# PiAndServos.net
KiCad netlist of a schematic drawn in Altium Designer
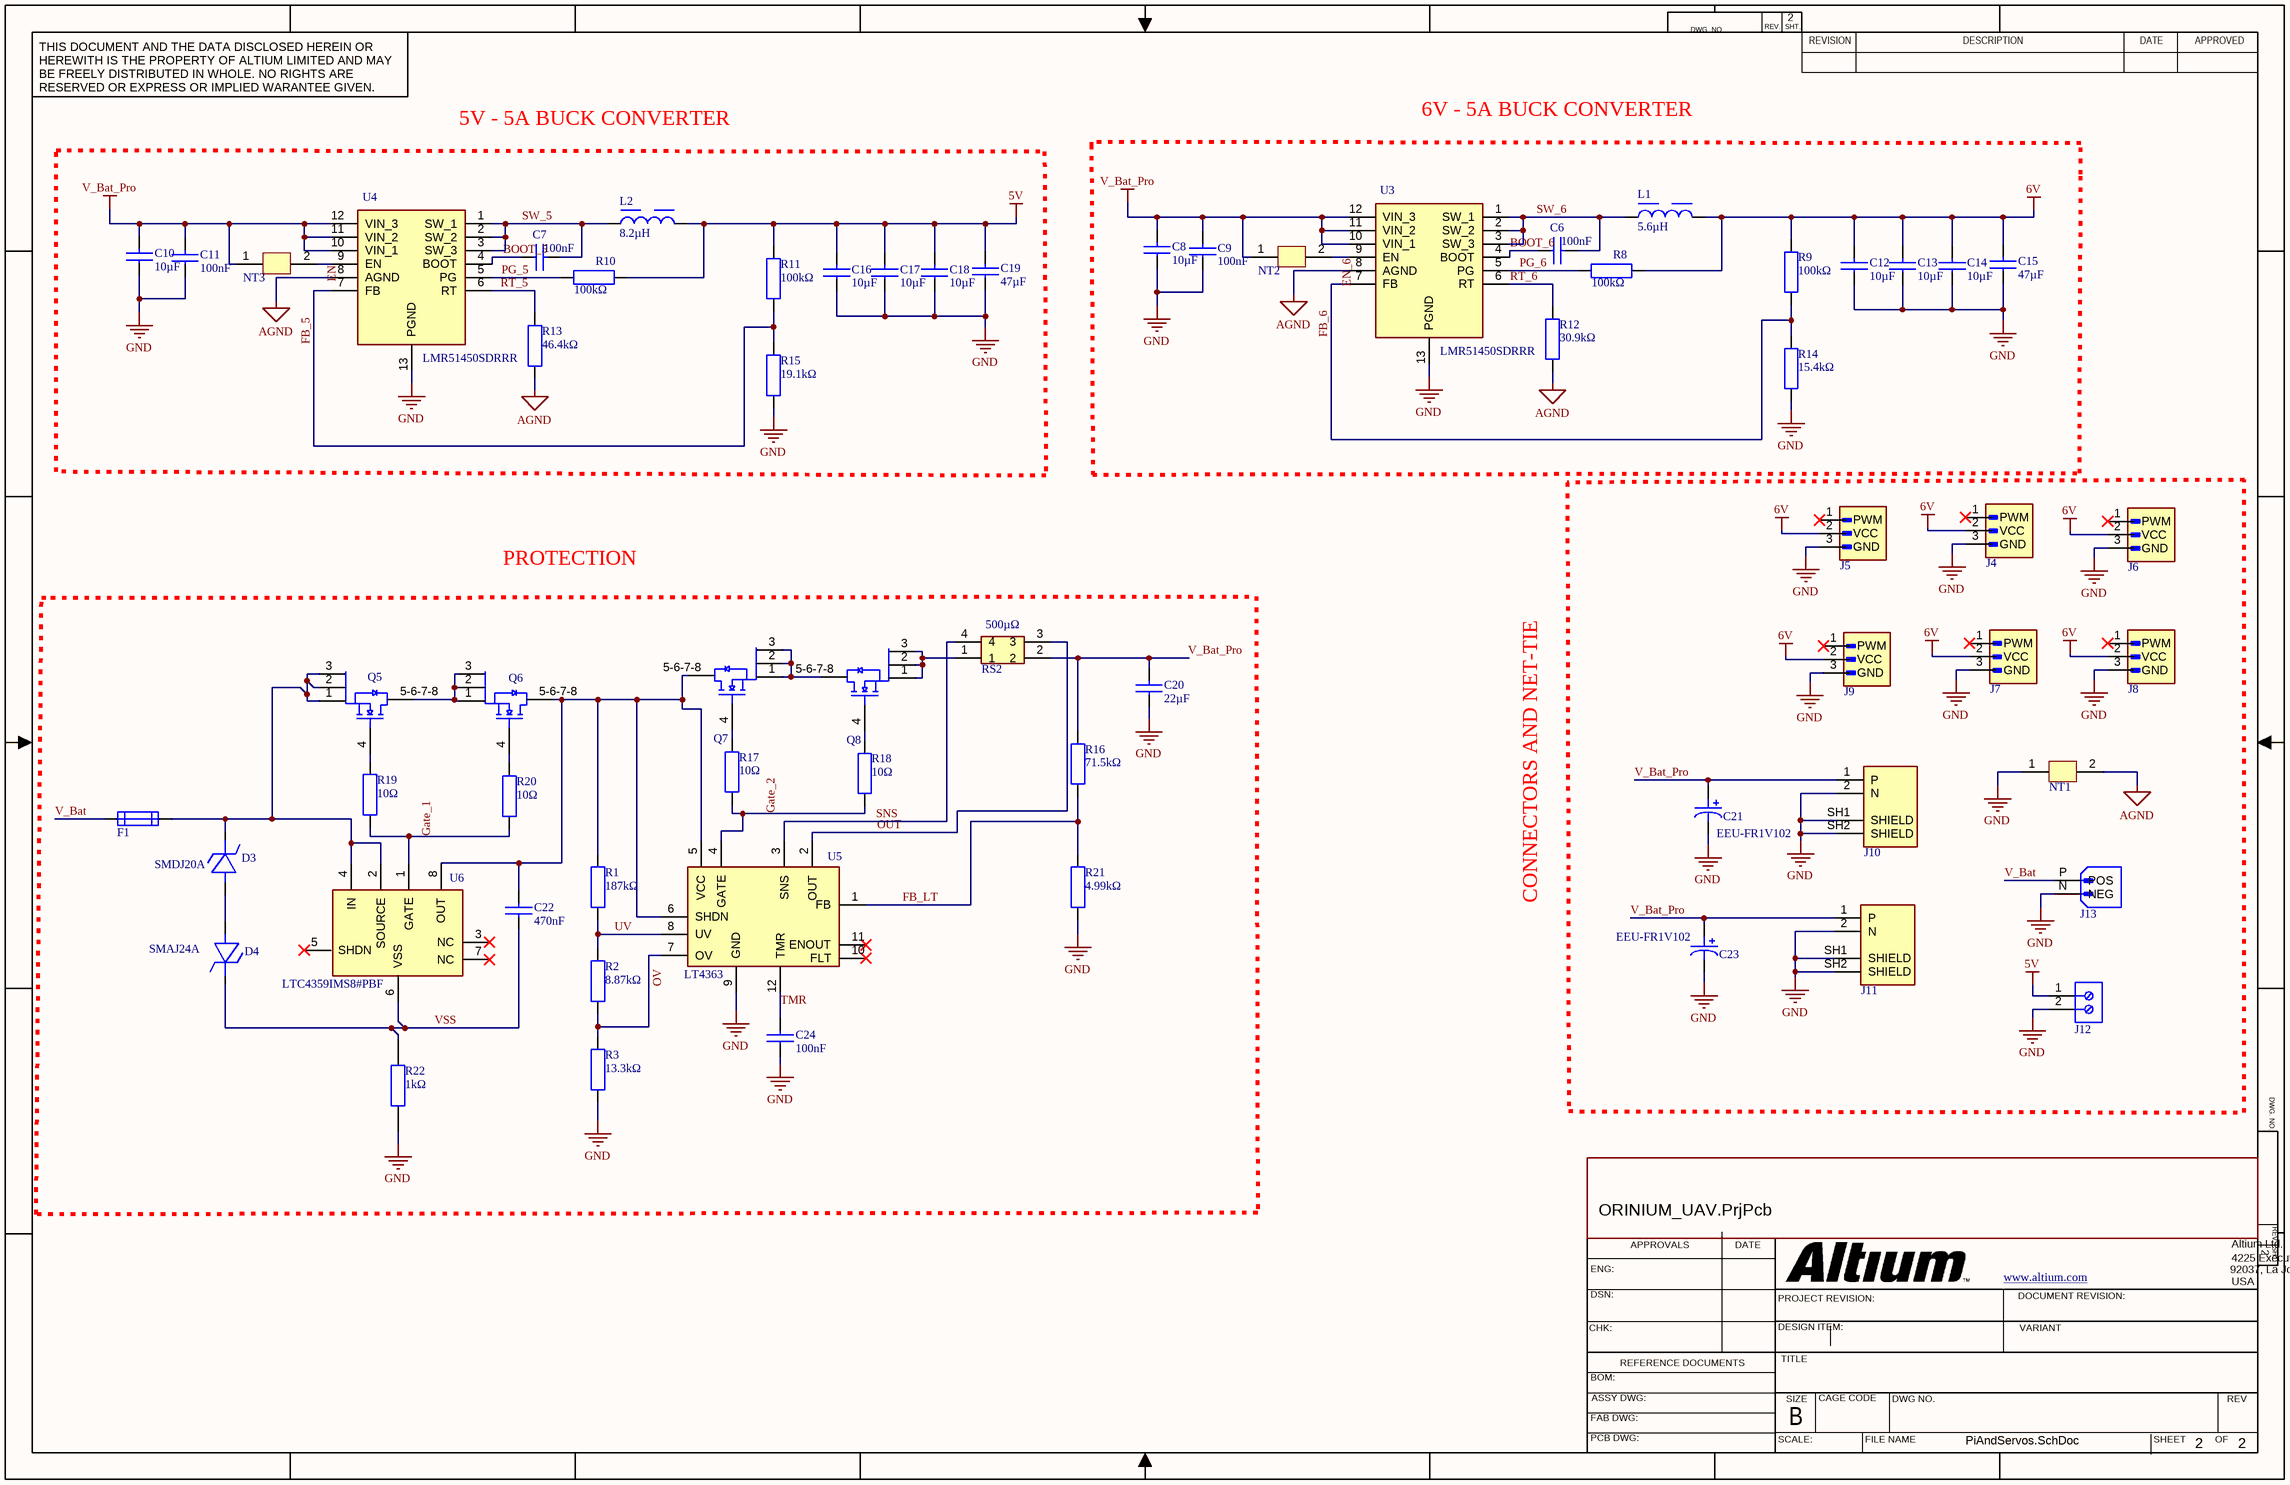
[diagram p0: PiAndServos.SchDoc]

(export (version "E")
  (design (tool "Eeschema 10.0.6"))
  (components
    (comp (ref "C6")
      (value "100nF")
      (footprint "CAP 0402")
      (description "16V 100nF X7R ±10% 0402 Multilayer Ceramic Capacitors MLCC - SMD/SMT ROHS")
      (fields
        (field (name "MANUFACTURER") "Murata")
        (field (name "MANUFACTURER PART NUMBER") "GRM155R71C104KA88D")
      )
      (libsource (lib "UAV") (part "GRM155R71C104KA88D"))
    )
    (comp (ref "C7")
      (value "100nF")
      (footprint "CAP 0402")
      (description "16V 100nF X7R ±10% 0402 Multilayer Ceramic Capacitors MLCC - SMD/SMT ROHS")
      (fields
        (field (name "MANUFACTURER") "Murata")
        (field (name "MANUFACTURER PART NUMBER") "GRM155R71C104KA88D")
      )
      (libsource (lib "UAV") (part "GRM155R71C104KA88D"))
    )
    (comp (ref "C8")
      (value "10µF")
      (footprint "CAP 1210")
      (description "50V 10uF X7R 卤20% 1210 Multilayer Ceramic Capacitors MLCC - SMD/SMT ROHS")
      (fields
        (field (name "MANUFACTURER") "TDK")
        (field (name "MANUFACTURER PART NUMBER") "C3225X7R1H106M250AC")
      )
      (libsource (lib "UAV") (part "C3225X7R1H106M250AC"))
    )
    (comp (ref "C9")
      (value "100nF")
      (footprint "CAP 0603")
      (description "Multilayer Ceramic Capacitor, CC Series, 0.1 - F, - 10%, X7R, 50 V, 0603 [1608 Metric]")
      (fields
        (field (name "MANUFACTURER") "Yageo Group")
        (field (name "MANUFACTURER PART NUMBER") "CC0603KRX7R9BB104")
      )
      (libsource (lib "UAV") (part "CC0603KRX7R9BB104"))
    )
    (comp (ref "C10")
      (value "10µF")
      (footprint "CAP 1210")
      (description "50V 10uF X7R 卤20% 1210 Multilayer Ceramic Capacitors MLCC - SMD/SMT ROHS")
      (fields
        (field (name "MANUFACTURER") "TDK")
        (field (name "MANUFACTURER PART NUMBER") "C3225X7R1H106M250AC")
      )
      (libsource (lib "UAV") (part "C3225X7R1H106M250AC"))
    )
    (comp (ref "C11")
      (value "100nF")
      (footprint "CAP 0603")
      (description "Multilayer Ceramic Capacitor, CC Series, 0.1 - F, - 10%, X7R, 50 V, 0603 [1608 Metric]")
      (fields
        (field (name "MANUFACTURER") "Yageo Group")
        (field (name "MANUFACTURER PART NUMBER") "CC0603KRX7R9BB104")
      )
      (libsource (lib "UAV") (part "CC0603KRX7R9BB104"))
    )
    (comp (ref "C12")
      (value "10µF")
      (footprint "CAP 1210")
      (description "50V 10uF X7R 卤20% 1210 Multilayer Ceramic Capacitors MLCC - SMD/SMT ROHS")
      (fields
        (field (name "MANUFACTURER") "TDK")
        (field (name "MANUFACTURER PART NUMBER") "C3225X7R1H106M250AC")
      )
      (libsource (lib "UAV") (part "C3225X7R1H106M250AC"))
    )
    (comp (ref "C13")
      (value "10µF")
      (footprint "CAP 1210")
      (description "50V 10uF X7R 卤20% 1210 Multilayer Ceramic Capacitors MLCC - SMD/SMT ROHS")
      (fields
        (field (name "MANUFACTURER") "TDK")
        (field (name "MANUFACTURER PART NUMBER") "C3225X7R1H106M250AC")
      )
      (libsource (lib "UAV") (part "C3225X7R1H106M250AC"))
    )
    (comp (ref "C14")
      (value "10µF")
      (footprint "CAP 1210")
      (description "50V 10uF X7R 卤20% 1210 Multilayer Ceramic Capacitors MLCC - SMD/SMT ROHS")
      (fields
        (field (name "MANUFACTURER") "TDK")
        (field (name "MANUFACTURER PART NUMBER") "C3225X7R1H106M250AC")
      )
      (libsource (lib "UAV") (part "C3225X7R1H106M250AC"))
    )
    (comp (ref "C15")
      (value "47µF")
      (footprint "CAP 1210")
      (description "16V 47uF X5R ±10% 1210 Multilayer Ceramic Capacitors MLCC - SMD/SMT ROHS")
      (fields
        (field (name "MANUFACTURER") "Murata")
        (field (name "MANUFACTURER PART NUMBER") "GRM32ER61C476KE15L")
      )
      (libsource (lib "UAV") (part "GRM32ER61C476KE15L"))
    )
    (comp (ref "C16")
      (value "10µF")
      (footprint "CAP 1210")
      (description "50V 10uF X7R 卤20% 1210 Multilayer Ceramic Capacitors MLCC - SMD/SMT ROHS")
      (fields
        (field (name "MANUFACTURER") "TDK")
        (field (name "MANUFACTURER PART NUMBER") "C3225X7R1H106M250AC")
      )
      (libsource (lib "UAV") (part "C3225X7R1H106M250AC"))
    )
    (comp (ref "C17")
      (value "10µF")
      (footprint "CAP 1210")
      (description "50V 10uF X7R 卤20% 1210 Multilayer Ceramic Capacitors MLCC - SMD/SMT ROHS")
      (fields
        (field (name "MANUFACTURER") "TDK")
        (field (name "MANUFACTURER PART NUMBER") "C3225X7R1H106M250AC")
      )
      (libsource (lib "UAV") (part "C3225X7R1H106M250AC"))
    )
    (comp (ref "C18")
      (value "10µF")
      (footprint "CAP 1210")
      (description "50V 10uF X7R 卤20% 1210 Multilayer Ceramic Capacitors MLCC - SMD/SMT ROHS")
      (fields
        (field (name "MANUFACTURER") "TDK")
        (field (name "MANUFACTURER PART NUMBER") "C3225X7R1H106M250AC")
      )
      (libsource (lib "UAV") (part "C3225X7R1H106M250AC"))
    )
    (comp (ref "C19")
      (value "47µF")
      (footprint "CAP 1210")
      (description "16V 47uF X5R ±10% 1210 Multilayer Ceramic Capacitors MLCC - SMD/SMT ROHS")
      (fields
        (field (name "MANUFACTURER") "Murata")
        (field (name "MANUFACTURER PART NUMBER") "GRM32ER61C476KE15L")
      )
      (libsource (lib "UAV") (part "GRM32ER61C476KE15L"))
    )
    (comp (ref "C20")
      (value "22µF")
      (footprint "CAP 2220")
      (description "50V 22uF X7R 卤20% 2220 Multilayer Ceramic Capacitors MLCC - SMD/SMT ROHS")
      (fields
        (field (name "MANUFACTURER") "TDK")
        (field (name "MANUFACTURER PART NUMBER") "C5750X7R1H226M250KB")
      )
      (libsource (lib "UAV") (part "C5750X7R1H226M250KB"))
    )
    (comp (ref "C21")
      (value "EEU-FR1V102")
      (footprint "CAP ALUM THT")
      (description "Radial Can ALUMINUM ELECTROLYTIC CAPACITOR FR 35V 1000muF ±20% 0.492Dia 12.50mm")
      (fields
        (field (name "MANUFACTURER") "Panasonic")
        (field (name "MANUFACTURER PART NUMBER") "EEUFR1V102")
      )
      (libsource (lib "UAV") (part "EEU-FR1V102"))
    )
    (comp (ref "C22")
      (value "470nF")
      (footprint "CAP 0603")
      (description "0612/0805/1206 Feedthru Ceramic Capacitors 1206 50V 47000pF")
      (fields
        (field (name "MANUFACTURER") "TAIYO YUDEN")
        (field (name "MANUFACTURER PART NUMBER") "MCASU168SB7474KTCA01")
      )
      (libsource (lib "UAV") (part "W3F15C4738AT1F"))
    )
    (comp (ref "C23")
      (value "EEU-FR1V102")
      (footprint "CAP ALUM THT")
      (description "Radial Can ALUMINUM ELECTROLYTIC CAPACITOR FR 35V 1000muF ±20% 0.492Dia 12.50mm")
      (fields
        (field (name "MANUFACTURER") "Panasonic")
        (field (name "MANUFACTURER PART NUMBER") "EEUFR1V102")
      )
      (libsource (lib "UAV") (part "EEU-FR1V102"))
    )
    (comp (ref "C24")
      (value "100nF")
      (footprint "CAP 0402")
      (description "16V 100nF X7R ±10% 0402 Multilayer Ceramic Capacitors MLCC - SMD/SMT ROHS")
      (fields
        (field (name "MANUFACTURER") "Murata")
        (field (name "MANUFACTURER PART NUMBER") "GRM155R71C104KA88D")
      )
      (libsource (lib "UAV") (part "GRM155R71C104KA88D"))
    )
    (comp (ref "D3")
      (value "SMDJ20A")
      (footprint "SMC (DO-214AB)")
      (description "SMDJ Series 20 V 3000 W Surface Mount Uni-Directional TVS Diode - DO-214AB")
      (fields (field (name "MANUFACTURER") "Littelfuse"))
      (libsource (lib "UAV") (part "SMDJ20A"))
    )
    (comp (ref "D4")
      (value "SMAJ24A")
      (footprint "SMA (DO-214AC)")
      (description "SMAJ Series 400 W 24 V Uni-Directional Surface Mount TVS Diode - DO-214AC")
      (fields (field (name "MANUFACTURER") "Littelfuse"))
      (libsource (lib "UAV") (part "SMAJ24A"))
    )
    (comp (ref "F1")
      (value "SF-3812F6000T-2")
      (footprint "SF-3812F6000T-2")
      (description "SMD Fuse, Fast Acting, 60 A, 250 VAC, 100 VDC, 3812 [10030 Metric], SF-3812F-T")
      (fields (field (name "MANUFACTURER") "Bourns"))
      (libsource (lib "UAV") (part "SF-3812F6000T-2"))
    )
    (comp (ref "J4")
      (value "61300311121")
      (footprint "1X3 MALE HEADER")
      (description "WR-PHD Straight Male, PCB Header, Through Hole, 1 Rows, 3 Contacts, 2.54mm Pitch")
      (fields (field (name "MANUFACTURER") "Wurth Elektronik"))
      (libsource (lib "UAV") (part "61300311121"))
    )
    (comp (ref "J5")
      (value "61300311121")
      (footprint "1X3 MALE HEADER")
      (description "WR-PHD Straight Male, PCB Header, Through Hole, 1 Rows, 3 Contacts, 2.54mm Pitch")
      (fields (field (name "MANUFACTURER") "Wurth Elektronik"))
      (libsource (lib "UAV") (part "61300311121"))
    )
    (comp (ref "J6")
      (value "61300311121")
      (footprint "1X3 MALE HEADER")
      (description "WR-PHD Straight Male, PCB Header, Through Hole, 1 Rows, 3 Contacts, 2.54mm Pitch")
      (fields (field (name "MANUFACTURER") "Wurth Elektronik"))
      (libsource (lib "UAV") (part "61300311121"))
    )
    (comp (ref "J7")
      (value "61300311121")
      (footprint "1X3 MALE HEADER")
      (description "WR-PHD Straight Male, PCB Header, Through Hole, 1 Rows, 3 Contacts, 2.54mm Pitch")
      (fields (field (name "MANUFACTURER") "Wurth Elektronik"))
      (libsource (lib "UAV") (part "61300311121"))
    )
    (comp (ref "J8")
      (value "61300311121")
      (footprint "1X3 MALE HEADER")
      (description "WR-PHD Straight Male, PCB Header, Through Hole, 1 Rows, 3 Contacts, 2.54mm Pitch")
      (fields (field (name "MANUFACTURER") "Wurth Elektronik"))
      (libsource (lib "UAV") (part "61300311121"))
    )
    (comp (ref "J9")
      (value "61300311121")
      (footprint "1X3 MALE HEADER")
      (description "WR-PHD Straight Male, PCB Header, Through Hole, 1 Rows, 3 Contacts, 2.54mm Pitch")
      (fields (field (name "MANUFACTURER") "Wurth Elektronik"))
      (libsource (lib "UAV") (part "61300311121"))
    )
    (comp (ref "J10")
      (value "XT60PW-M")
      (footprint "XT60PW-M")
      (fields (field (name "MANUFACTURER") "Amass"))
      (libsource (lib "UAV") (part "XT60PW-M"))
    )
    (comp (ref "J11")
      (value "XT60PW-M")
      (footprint "XT60PW-M")
      (fields (field (name "MANUFACTURER") "Amass"))
      (libsource (lib "UAV") (part "XT60PW-M"))
    )
    (comp (ref "J12")
      (value "1725656")
      (footprint "1725656")
      (description "Block, Terminal; 6 A; 63 V; 2.54 mm; 26 to 20 AWG; 2; Screw; Soldering; 1.5 kV")
      (fields (field (name "MANUFACTURER") "Phoenix Contact") (field (name "VOLTAGE") "125V"))
      (libsource (lib "UAV") (part "1725656"))
    )
    (comp (ref "J13") (value "XT90-S") (footprint "XT90") (libsource (lib "UAV") (part "XT90-S")))
    (comp (ref "L1")
      (value "5.6µH")
      (footprint "XAL6060-822MEB")
      (description "General Purpose Inductor, 5.6uH, 20%, 1 Element, Composite-Core, SMD, 2625")
      (fields
        (field (name "MANUFACTURER") "Coilcraft")
        (field (name "MANUFACTURER PART NUMBER") "XAL6060-562MEB")
      )
      (libsource (lib "UAV") (part "XAL6060-562MEB"))
    )
    (comp (ref "L2")
      (value "8.2µH")
      (footprint "XAL6060-822MEB")
      (description "XAL6060-822MEB")
      (fields (field (name "MANUFACTURER") "Coilcraft") (field (name "TOLERANCE") "20%"))
      (libsource (lib "UAV") (part "XAL6060-822MEB"))
    )
    (comp (ref "NT1") (value "Net-Tie") (footprint "Net-Tie") (libsource (lib "UAV") (part "Net-Tie")))
    (comp (ref "NT2") (value "Net-Tie") (footprint "Net-Tie") (libsource (lib "UAV") (part "Net-Tie")))
    (comp (ref "NT3") (value "Net-Tie") (footprint "Net-Tie") (libsource (lib "UAV") (part "Net-Tie")))
    (comp (ref "Q5")
      (value "BSC010N04LSI")
      (footprint "SON 5X6")
      (description "Transistor: N-MOSFET; unipolar; 40V; 100A; 139W; PG-TDSON-8")
      (fields
        (field (name "MANUFACTURER") "Infineon")
        (field (name "MANUFACTURER PART NUMBER") "BSC010N04LSIATMA1")
      )
      (libsource (lib "UAV") (part "BSC010N04LSI"))
    )
    (comp (ref "Q6")
      (value "BSC010N04LSI")
      (footprint "SON 5X6")
      (description "Transistor: N-MOSFET; unipolar; 40V; 100A; 139W; PG-TDSON-8")
      (fields
        (field (name "MANUFACTURER") "Infineon")
        (field (name "MANUFACTURER PART NUMBER") "BSC010N04LSIATMA1")
      )
      (libsource (lib "UAV") (part "BSC010N04LSI"))
    )
    (comp (ref "Q7")
      (value "BSC010N04LSI")
      (footprint "SON 5X6")
      (description "Transistor: N-MOSFET; unipolar; 40V; 100A; 139W; PG-TDSON-8")
      (fields
        (field (name "MANUFACTURER") "Infineon")
        (field (name "MANUFACTURER PART NUMBER") "BSC010N04LSIATMA1")
      )
      (libsource (lib "UAV") (part "BSC010N04LSI"))
    )
    (comp (ref "Q8")
      (value "BSC010N04LSI")
      (footprint "SON 5X6")
      (description "Transistor: N-MOSFET; unipolar; 40V; 100A; 139W; PG-TDSON-8")
      (fields
        (field (name "MANUFACTURER") "Infineon")
        (field (name "MANUFACTURER PART NUMBER") "BSC010N04LSIATMA1")
      )
      (libsource (lib "UAV") (part "BSC010N04LSI"))
    )
    (comp (ref "R1")
      (value "187kΩ")
      (footprint "RES 1206")
      (description "Res Thick Film 0805 187K Ohm 1% 0.125W(1/8W) ±100ppm/C Pad SMD T/R")
      (fields
        (field (name "MANUFACTURER") "Yageo Group")
        (field (name "MANUFACTURER PART NUMBER") "RC0805FR-07187KL")
      )
      (libsource (lib "UAV") (part "RC0805FR-07187KL"))
    )
    (comp (ref "R2")
      (value "8.87kΩ")
      (footprint "RES 1206")
      (description "Res Thick Film 0805 8.87K Ohm 1% 0.125W(1/8W) ±100ppm/C Pad SMD T/R")
      (fields
        (field (name "MANUFACTURER") "Yageo Group")
        (field (name "MANUFACTURER PART NUMBER") "RC0805FR-078K87L")
      )
      (libsource (lib "UAV") (part "RC0805FR-078K87L"))
    )
    (comp (ref "R3")
      (value "13.3kΩ")
      (footprint "RES 1206")
      (description "Res Thick Film 0805 13.3K Ohm 1% 0.125W(1/8W) ±100ppm/C Pad SMD T/R")
      (fields
        (field (name "MANUFACTURER") "Yageo Group")
        (field (name "MANUFACTURER PART NUMBER") "RC0805FR-0713K3L")
      )
      (libsource (lib "UAV") (part "RC0805FR-0713K3L"))
    )
    (comp (ref "R8")
      (value "100kΩ")
      (footprint "RES 0603")
      (description "100mW Thick Film Resistors 75V ±100ppm/℃ ±1% 100kΩ 0603 Chip Resistor - Surface Mount ROHS")
      (fields
        (field (name "MANUFACTURER") "Vishay")
        (field (name "MANUFACTURER PART NUMBER") "CRCW0603100KFKEAC")
      )
      (libsource (lib "UAV") (part "CRCW0603100KFKEA"))
    )
    (comp (ref "R9")
      (value "100kΩ")
      (footprint "RES 0402")
      (description "63mW Thick Film Resistors 75V ±1% ±100ppm/℃ 100kΩ 0402 Chip Resistor - Surface Mount ROHS")
      (fields
        (field (name "MANUFACTURER") "Vishay")
        (field (name "MANUFACTURER PART NUMBER") "CRCW0402100KFKED")
      )
      (libsource (lib "UAV") (part "CRCW0402100KFKED"))
    )
    (comp (ref "R10")
      (value "100kΩ")
      (footprint "RES 0603")
      (description "100mW Thick Film Resistors 75V ±100ppm/℃ ±1% 100kΩ 0603 Chip Resistor - Surface Mount ROHS")
      (fields
        (field (name "MANUFACTURER") "Vishay")
        (field (name "MANUFACTURER PART NUMBER") "CRCW0603100KFKEAC")
      )
      (libsource (lib "UAV") (part "CRCW0603100KFKEA"))
    )
    (comp (ref "R11")
      (value "100kΩ")
      (footprint "RES 0402")
      (description "63mW Thick Film Resistors 75V ±1% ±100ppm/℃ 100kΩ 0402 Chip Resistor - Surface Mount ROHS")
      (fields
        (field (name "MANUFACTURER") "Vishay")
        (field (name "MANUFACTURER PART NUMBER") "CRCW0402100KFKED")
      )
      (libsource (lib "UAV") (part "CRCW0402100KFKED"))
    )
    (comp (ref "R12")
      (value "30.9kΩ")
      (footprint "RES 0402")
      (description "Fixed Resistor, Metal Glaze/Thick Film, 0.063W, 30900ohm, 50V, 1% +/-Tol, Surface Mount, 0402")
      (fields
        (field (name "MANUFACTURER") "Vishay")
        (field (name "MANUFACTURER PART NUMBER") "CRCW040230K9FKED")
      )
      (libsource (lib "UAV") (part "CRCW040230K9FKED"))
    )
    (comp (ref "R13")
      (value "46.4kΩ")
      (footprint "RES 0603")
      (description "Fixed Resistor, Metal Glaze/Thick Film, 0.1W, 46400ohm, 75V, 1% +/-Tol, Surface Mount, 0603")
      (fields
        (field (name "MANUFACTURER") "Vishay")
        (field (name "MANUFACTURER PART NUMBER") "CRCW060346K4FKEA")
      )
      (libsource (lib "UAV") (part "CRCW060346K4FKEA"))
    )
    (comp (ref "R14")
      (value "15.4kΩ")
      (footprint "RES 0402")
      (description "Res Thick Film 0402 15.4K Ohm 1% 0.063W(1/16W) ±100ppm/C Pad SMD Automotive T/R")
      (fields
        (field (name "MANUFACTURER") "Yageo Group")
        (field (name "MANUFACTURER PART NUMBER") "AC0402FR-0715K4L")
      )
      (libsource (lib "UAV") (part "AC0402FR-0715K4L"))
    )
    (comp (ref "R15")
      (value "19.1kΩ")
      (footprint "RES 0402")
      (description "Res Thick Film 0402 19.1K Ohm 1% 1/16W ±100ppm/°C Molded SMD SMD Paper T/R")
      (fields
        (field (name "MANUFACTURER") "Vishay")
        (field (name "MANUFACTURER PART NUMBER") "CRCW040219K1FKED")
      )
      (libsource (lib "UAV") (part "CRCW040219K1FKED"))
    )
    (comp (ref "R16")
      (value "71.5kΩ")
      (footprint "RES 0603")
      (description "Res Thick Film 0603 71.5K Ohm 1% 0.1W(1/10W) ±100ppm/C Pad SMD T/R")
      (fields
        (field (name "MANUFACTURER") "Yageo Group")
        (field (name "MANUFACTURER PART NUMBER") "RC0603FR-0771K5L")
      )
      (libsource (lib "UAV") (part "RC0603FR-0771K5L"))
    )
    (comp (ref "R17")
      (value "10Ω")
      (footprint "SR0805FR-7W10RL")
      (description "Res Thick Film 0805 10 Ohm 1% 0.25W(1/4W) ±200ppm/C Pad SMD Automotive T/R")
      (fields
        (field (name "MANUFACTURER") "Yageo Group")
        (field (name "MANUFACTURER PART NUMBER") "SR0805FR-7W10RL")
      )
      (libsource (lib "UAV") (part "SR0805FR-7W10RL"))
    )
    (comp (ref "R18")
      (value "10Ω")
      (footprint "SR0805FR-7W10RL")
      (description "Res Thick Film 0805 10 Ohm 1% 0.25W(1/4W) ±200ppm/C Pad SMD Automotive T/R")
      (fields
        (field (name "MANUFACTURER") "Yageo Group")
        (field (name "MANUFACTURER PART NUMBER") "SR0805FR-7W10RL")
      )
      (libsource (lib "UAV") (part "SR0805FR-7W10RL"))
    )
    (comp (ref "R19")
      (value "10Ω")
      (footprint "SR0805FR-7W10RL")
      (description "Res Thick Film 0805 10 Ohm 1% 0.25W(1/4W) ±200ppm/C Pad SMD Automotive T/R")
      (fields
        (field (name "MANUFACTURER") "Yageo Group")
        (field (name "MANUFACTURER PART NUMBER") "SR0805FR-7W10RL")
      )
      (libsource (lib "UAV") (part "SR0805FR-7W10RL"))
    )
    (comp (ref "R20")
      (value "10Ω")
      (footprint "SR0805FR-7W10RL")
      (description "Res Thick Film 0805 10 Ohm 1% 0.25W(1/4W) ±200ppm/C Pad SMD Automotive T/R")
      (fields
        (field (name "MANUFACTURER") "Yageo Group")
        (field (name "MANUFACTURER PART NUMBER") "SR0805FR-7W10RL")
      )
      (libsource (lib "UAV") (part "SR0805FR-7W10RL"))
    )
    (comp (ref "R21")
      (value "4.99kΩ")
      (footprint "RES 0402")
      (description "Res Thick Film 0402 4.99K Ohm 1% 0.1W(1/10W) ±100ppm/C Pad SMD Automotive T/R")
      (fields
        (field (name "MANUFACTURER") "Panasonic")
        (field (name "MANUFACTURER PART NUMBER") "ERJ2RKF4991X")
      )
      (libsource (lib "UAV") (part "ERJ-2RKF4991X"))
    )
    (comp (ref "R22")
      (value "1kΩ")
      (footprint "RES 1206")
      (fields
        (field (name "MANUFACTURER") "Yageo Group")
        (field (name "MANUFACTURER PART NUMBER") "SR1206FR-071KL")
        (field (name "TOLERANCE") "1%")
      )
      (libsource (lib "UAV") (part "SR1206FR-071KL"))
    )
    (comp (ref "RS2")
      (value "500µΩ")
      (footprint "SR_4026")
      (description "Res Metal Strip 4026 0.0005 Ohm 1% 7W ±75ppm/C Metal Pad SMD Automotive T/R")
      (fields
        (field (name "MANUFACTURER") "Vishay")
        (field (name "MANUFACTURER PART NUMBER") "WSLP4026L5000FEA")
      )
      (libsource (lib "UAV") (part "WSLP4026L5000FEA"))
    )
    (comp (ref "U3")
      (value "LMR51450SDRRR")
      (footprint "WSON -12")
      (description "36-V, 5-A synchronous buck converter 12-WSON -40 to 150")
      (fields (field (name "MANUFACTURER") "Texas Instruments"))
      (libsource (lib "UAV") (part "LMR51450SDRRR"))
    )
    (comp (ref "U4")
      (value "LMR51450SDRRR")
      (footprint "WSON -12")
      (description "36-V, 5-A synchronous buck converter 12-WSON -40 to 150")
      (fields (field (name "MANUFACTURER") "Texas Instruments"))
      (libsource (lib "UAV") (part "LMR51450SDRRR"))
    )
    (comp (ref "U5")
      (value "LT4363")
      (footprint "MSOP-12")
      (description "Circuit Protection Misc High Voltage Surge Stopper with Current Limit")
      (fields
        (field (name "MANUFACTURER") "Analog Devices")
        (field (name "MANUFACTURER PART NUMBER") "LT4363MPMS-1#TRPBF")
      )
      (libsource (lib "UAV") (part "LT4363IMS-2#PBF"))
    )
    (comp (ref "U6")
      (value "LTC4359IMS8#PBF")
      (footprint "MSOP-8")
      (description "OR Controller N-Channel Single Automotive 8-Pin MSOP Tube / IC OR CTRLR N+1 8MSOP")
      (fields (field (name "MANUFACTURER") "Analog Devices"))
      (libsource (lib "UAV") (part "LTC4359IMS8#PBF"))
    )
  )
  (nets
    (net (code "1") (name "/BOOT_5") (class "Default")
      (node (ref "C7") (pin "1") (pinfunction "1_1") (pintype "passive"))
      (node (ref "U4") (pin "4") (pinfunction "BOOT_4") (pintype "passive"))
    )
    (net (code "2") (name "/BOOT_6") (class "Default")
      (node (ref "C6") (pin "1") (pinfunction "1_1") (pintype "passive"))
      (node (ref "U3") (pin "4") (pinfunction "BOOT_4") (pintype "passive"))
    )
    (net (code "3") (name "/EN") (class "Default")
      (node (ref "NT3") (pin "2") (pinfunction "2_2") (pintype "passive"))
      (node (ref "U4") (pin "9") (pinfunction "EN_9") (pintype "passive"))
    )
    (net (code "4") (name "/EN_6") (class "Default")
      (node (ref "NT2") (pin "2") (pinfunction "2_2") (pintype "passive"))
      (node (ref "U3") (pin "9") (pinfunction "EN_9") (pintype "passive"))
    )
    (net (code "5") (name "/FB_5") (class "Default")
      (node (ref "R11") (pin "1") (pinfunction "1_1") (pintype "passive"))
      (node (ref "R15") (pin "2") (pinfunction "2_2") (pintype "passive"))
      (node (ref "U4") (pin "7") (pinfunction "FB_7") (pintype "passive"))
    )
    (net (code "6") (name "/FB_6") (class "Default")
      (node (ref "R14") (pin "2") (pinfunction "2_2") (pintype "passive"))
      (node (ref "R9") (pin "1") (pinfunction "1_1") (pintype "passive"))
      (node (ref "U3") (pin "7") (pinfunction "FB_7") (pintype "passive"))
    )
    (net (code "7") (name "/FB_LT") (class "Default")
      (node (ref "R16") (pin "1") (pinfunction "1_1") (pintype "passive"))
      (node (ref "R21") (pin "2") (pinfunction "2_2") (pintype "passive"))
      (node (ref "U5") (pin "1") (pinfunction "FB_1") (pintype "passive"))
    )
    (net (code "8") (name "/Gate_1") (class "Default")
      (node (ref "R19") (pin "1") (pinfunction "1_1") (pintype "passive"))
      (node (ref "R20") (pin "1") (pinfunction "1_1") (pintype "passive"))
      (node (ref "U6") (pin "1") (pinfunction "GATE_1") (pintype "passive"))
    )
    (net (code "9") (name "/Gate_2") (class "Default")
      (node (ref "R17") (pin "1") (pinfunction "1_1") (pintype "passive"))
      (node (ref "R18") (pin "1") (pinfunction "1_1") (pintype "passive"))
      (node (ref "U5") (pin "4") (pinfunction "GATE_4") (pintype "passive"))
    )
    (net (code "10") (name "/OUT") (class "Default")
      (node (ref "RS2") (pin "3") (pinfunction "3_3") (pintype "passive"))
      (node (ref "U5") (pin "2") (pinfunction "OUT_2") (pintype "passive"))
    )
    (net (code "11") (name "/OV") (class "Default")
      (node (ref "R2") (pin "1") (pinfunction "1_1") (pintype "passive"))
      (node (ref "R3") (pin "2") (pinfunction "2_2") (pintype "passive"))
      (node (ref "U5") (pin "7") (pinfunction "OV_7") (pintype "passive"))
    )
    (net (code "12") (name "/PG_5") (class "Default")
      (node (ref "R10") (pin "1") (pinfunction "1_1") (pintype "passive"))
      (node (ref "U4") (pin "5") (pinfunction "PG_5") (pintype "passive"))
    )
    (net (code "13") (name "/PG_6") (class "Default")
      (node (ref "R8") (pin "1") (pinfunction "1_1") (pintype "passive"))
      (node (ref "U3") (pin "5") (pinfunction "PG_5") (pintype "passive"))
    )
    (net (code "14") (name "/RT_5") (class "Default")
      (node (ref "R13") (pin "2") (pinfunction "2_2") (pintype "passive"))
      (node (ref "U4") (pin "6") (pinfunction "RT_6") (pintype "passive"))
    )
    (net (code "15") (name "/RT_6") (class "Default")
      (node (ref "R12") (pin "2") (pinfunction "2_2") (pintype "passive"))
      (node (ref "U3") (pin "6") (pinfunction "RT_6") (pintype "passive"))
    )
    (net (code "16") (name "/SNS") (class "Default")
      (node (ref "RS2") (pin "4") (pinfunction "4_4") (pintype "passive"))
      (node (ref "U5") (pin "3") (pinfunction "SNS_3") (pintype "passive"))
    )
    (net (code "17") (name "/SW_5") (class "Default")
      (node (ref "C7") (pin "2") (pinfunction "2_2") (pintype "passive"))
      (node (ref "L2") (pin "1") (pinfunction "1_1") (pintype "passive"))
      (node (ref "U4") (pin "1") (pinfunction "SW_1_1") (pintype "passive"))
      (node (ref "U4") (pin "2") (pinfunction "SW_2_2") (pintype "passive"))
      (node (ref "U4") (pin "3") (pinfunction "SW_3_3") (pintype "passive"))
    )
    (net (code "18") (name "/SW_6") (class "Default")
      (node (ref "C6") (pin "2") (pinfunction "2_2") (pintype "passive"))
      (node (ref "L1") (pin "1") (pinfunction "1_1") (pintype "passive"))
      (node (ref "U3") (pin "1") (pinfunction "SW_1_1") (pintype "passive"))
      (node (ref "U3") (pin "2") (pinfunction "SW_2_2") (pintype "passive"))
      (node (ref "U3") (pin "3") (pinfunction "SW_3_3") (pintype "passive"))
    )
    (net (code "19") (name "/TMR") (class "Default")
      (node (ref "C24") (pin "2") (pinfunction "2_2") (pintype "passive"))
      (node (ref "U5") (pin "12") (pinfunction "TMR_12") (pintype "passive"))
    )
    (net (code "20") (name "/UV") (class "Default")
      (node (ref "R1") (pin "2") (pinfunction "2_2") (pintype "passive"))
      (node (ref "R2") (pin "2") (pinfunction "2_2") (pintype "passive"))
      (node (ref "U5") (pin "8") (pinfunction "UV_8") (pintype "passive"))
    )
    (net (code "21") (name "/VSS") (class "Default")
      (node (ref "C22") (pin "1") (pinfunction "1_1") (pintype "passive"))
      (node (ref "D4") (pin "1") (pinfunction "1_1") (pintype "passive"))
      (node (ref "R22") (pin "2") (pinfunction "2_2") (pintype "passive"))
      (node (ref "U6") (pin "6") (pinfunction "VSS_6") (pintype "passive"))
    )
    (net (code "22") (name "/V_Bat") (class "Default")
      (node (ref "F1") (pin "1") (pinfunction "1_1") (pintype "passive"))
      (node (ref "J13") (pin "P") (pinfunction "POS_P") (pintype "passive"))
    )
    (net (code "23") (name "5V") (class "Default")
      (node (ref "C16") (pin "2") (pinfunction "2_2") (pintype "passive"))
      (node (ref "C17") (pin "2") (pinfunction "2_2") (pintype "passive"))
      (node (ref "C18") (pin "2") (pinfunction "2_2") (pintype "passive"))
      (node (ref "C19") (pin "2") (pinfunction "2_2") (pintype "passive"))
      (node (ref "J12") (pin "1") (pinfunction "VCC_1") (pintype "passive"))
      (node (ref "L2") (pin "2") (pinfunction "2_2") (pintype "passive"))
      (node (ref "R10") (pin "2") (pinfunction "2_2") (pintype "passive"))
      (node (ref "R11") (pin "2") (pinfunction "2_2") (pintype "passive"))
    )
    (net (code "24") (name "6V") (class "Default")
      (node (ref "C12") (pin "2") (pinfunction "2_2") (pintype "passive"))
      (node (ref "C13") (pin "2") (pinfunction "2_2") (pintype "passive"))
      (node (ref "C14") (pin "2") (pinfunction "2_2") (pintype "passive"))
      (node (ref "C15") (pin "2") (pinfunction "2_2") (pintype "passive"))
      (node (ref "J4") (pin "2") (pinfunction "VCC_2") (pintype "passive"))
      (node (ref "J5") (pin "2") (pinfunction "VCC_2") (pintype "passive"))
      (node (ref "J6") (pin "2") (pinfunction "VCC_2") (pintype "passive"))
      (node (ref "J7") (pin "2") (pinfunction "VCC_2") (pintype "passive"))
      (node (ref "J8") (pin "2") (pinfunction "VCC_2") (pintype "passive"))
      (node (ref "J9") (pin "2") (pinfunction "VCC_2") (pintype "passive"))
      (node (ref "L1") (pin "2") (pinfunction "2_2") (pintype "passive"))
      (node (ref "R8") (pin "2") (pinfunction "2_2") (pintype "passive"))
      (node (ref "R9") (pin "2") (pinfunction "2_2") (pintype "passive"))
    )
    (net (code "25") (name "AGND") (class "Default")
      (node (ref "NT1") (pin "2") (pinfunction "2_2") (pintype "passive"))
      (node (ref "R12") (pin "1") (pinfunction "1_1") (pintype "passive"))
      (node (ref "R13") (pin "1") (pinfunction "1_1") (pintype "passive"))
      (node (ref "U3") (pin "8") (pinfunction "AGND_8") (pintype "passive"))
      (node (ref "U4") (pin "8") (pinfunction "AGND_8") (pintype "passive"))
    )
    (net (code "26") (name "GND") (class "Default")
      (node (ref "C10") (pin "1") (pinfunction "1_1") (pintype "passive"))
      (node (ref "C11") (pin "1") (pinfunction "1_1") (pintype "passive"))
      (node (ref "C12") (pin "1") (pinfunction "1_1") (pintype "passive"))
      (node (ref "C13") (pin "1") (pinfunction "1_1") (pintype "passive"))
      (node (ref "C14") (pin "1") (pinfunction "1_1") (pintype "passive"))
      (node (ref "C15") (pin "1") (pinfunction "1_1") (pintype "passive"))
      (node (ref "C16") (pin "1") (pinfunction "1_1") (pintype "passive"))
      (node (ref "C17") (pin "1") (pinfunction "1_1") (pintype "passive"))
      (node (ref "C18") (pin "1") (pinfunction "1_1") (pintype "passive"))
      (node (ref "C19") (pin "1") (pinfunction "1_1") (pintype "passive"))
      (node (ref "C20") (pin "1") (pinfunction "1_1") (pintype "passive"))
      (node (ref "C21") (pin "2") (pinfunction "2_2") (pintype "passive"))
      (node (ref "C23") (pin "2") (pinfunction "2_2") (pintype "passive"))
      (node (ref "C24") (pin "1") (pinfunction "1_1") (pintype "passive"))
      (node (ref "C8") (pin "1") (pinfunction "1_1") (pintype "passive"))
      (node (ref "C9") (pin "1") (pinfunction "1_1") (pintype "passive"))
      (node (ref "J10") (pin "2") (pinfunction "N_2") (pintype "passive"))
      (node (ref "J10") (pin "SH1") (pinfunction "SHIELD_SH1") (pintype "passive"))
      (node (ref "J10") (pin "SH2") (pinfunction "SHIELD_SH2") (pintype "passive"))
      (node (ref "J11") (pin "2") (pinfunction "N_2") (pintype "passive"))
      (node (ref "J11") (pin "SH1") (pinfunction "SHIELD_SH1") (pintype "passive"))
      (node (ref "J11") (pin "SH2") (pinfunction "SHIELD_SH2") (pintype "passive"))
      (node (ref "J12") (pin "2") (pinfunction "GND_2") (pintype "passive"))
      (node (ref "J13") (pin "N") (pinfunction "NEG_N") (pintype "passive"))
      (node (ref "J4") (pin "3") (pinfunction "GND_3") (pintype "passive"))
      (node (ref "J5") (pin "3") (pinfunction "GND_3") (pintype "passive"))
      (node (ref "J6") (pin "3") (pinfunction "GND_3") (pintype "passive"))
      (node (ref "J7") (pin "3") (pinfunction "GND_3") (pintype "passive"))
      (node (ref "J8") (pin "3") (pinfunction "GND_3") (pintype "passive"))
      (node (ref "J9") (pin "3") (pinfunction "GND_3") (pintype "passive"))
      (node (ref "NT1") (pin "1") (pinfunction "1_1") (pintype "passive"))
      (node (ref "R14") (pin "1") (pinfunction "1_1") (pintype "passive"))
      (node (ref "R15") (pin "1") (pinfunction "1_1") (pintype "passive"))
      (node (ref "R21") (pin "1") (pinfunction "1_1") (pintype "passive"))
      (node (ref "R22") (pin "1") (pinfunction "1_1") (pintype "passive"))
      (node (ref "R3") (pin "1") (pinfunction "1_1") (pintype "passive"))
      (node (ref "U3") (pin "13") (pinfunction "PGND_13") (pintype "passive"))
      (node (ref "U4") (pin "13") (pinfunction "PGND_13") (pintype "passive"))
      (node (ref "U5") (pin "9") (pinfunction "GND_9") (pintype "passive"))
    )
    (net (code "27") (name "Net-(D3-Pad2)") (class "Default")
      (node (ref "D3") (pin "2") (pinfunction "2_2") (pintype "passive"))
      (node (ref "D4") (pin "2") (pinfunction "2_2") (pintype "passive"))
    )
    (net (code "28") (name "Net-(Q5-D)") (class "Default")
      (node (ref "Q5") (pin "5-6-7-8") (pinfunction "D_5-6-7-8") (pintype "passive"))
      (node (ref "Q6") (pin "1") (pinfunction "S_1") (pintype "passive"))
      (node (ref "Q6") (pin "2") (pinfunction "S_2") (pintype "passive"))
      (node (ref "Q6") (pin "3") (pinfunction "S_3") (pintype "passive"))
    )
    (net (code "29") (name "Net-(Q5-G)") (class "Default")
      (node (ref "Q5") (pin "4") (pinfunction "G_4") (pintype "passive"))
      (node (ref "R19") (pin "2") (pinfunction "2_2") (pintype "passive"))
    )
    (net (code "30") (name "Net-(Q6-D)") (class "Default")
      (node (ref "C22") (pin "2") (pinfunction "2_2") (pintype "passive"))
      (node (ref "Q6") (pin "5-6-7-8") (pinfunction "D_5-6-7-8") (pintype "passive"))
      (node (ref "Q7") (pin "5-6-7-8") (pinfunction "D_5-6-7-8") (pintype "passive"))
      (node (ref "R1") (pin "1") (pinfunction "1_1") (pintype "passive"))
      (node (ref "U5") (pin "5") (pinfunction "VCC_5") (pintype "passive"))
      (node (ref "U5") (pin "6") (pinfunction "SHDN_6") (pintype "passive"))
      (node (ref "U6") (pin "8") (pinfunction "OUT_8") (pintype "passive"))
    )
    (net (code "31") (name "Net-(Q6-G)") (class "Default")
      (node (ref "Q6") (pin "4") (pinfunction "G_4") (pintype "passive"))
      (node (ref "R20") (pin "2") (pinfunction "2_2") (pintype "passive"))
    )
    (net (code "32") (name "Net-(Q7-G)") (class "Default")
      (node (ref "Q7") (pin "4") (pinfunction "G_4") (pintype "passive"))
      (node (ref "R17") (pin "2") (pinfunction "2_2") (pintype "passive"))
    )
    (net (code "33") (name "Net-(Q8-D)") (class "Default")
      (node (ref "Q7") (pin "1") (pinfunction "S_1") (pintype "passive"))
      (node (ref "Q7") (pin "2") (pinfunction "S_2") (pintype "passive"))
      (node (ref "Q7") (pin "3") (pinfunction "S_3") (pintype "passive"))
      (node (ref "Q8") (pin "5-6-7-8") (pinfunction "D_5-6-7-8") (pintype "passive"))
    )
    (net (code "34") (name "Net-(Q8-G)") (class "Default")
      (node (ref "Q8") (pin "4") (pinfunction "G_4") (pintype "passive"))
      (node (ref "R18") (pin "2") (pinfunction "2_2") (pintype "passive"))
    )
    (net (code "35") (name "Net-(Q8-S-Pad1)") (class "Default")
      (node (ref "Q8") (pin "1") (pinfunction "S_1") (pintype "passive"))
      (node (ref "Q8") (pin "2") (pinfunction "S_2") (pintype "passive"))
      (node (ref "Q8") (pin "3") (pinfunction "S_3") (pintype "passive"))
      (node (ref "RS2") (pin "1") (pinfunction "1_1") (pintype "passive"))
    )
    (net (code "36") (name "Net-(U6-IN)") (class "Default")
      (node (ref "D3") (pin "1") (pinfunction "1_1") (pintype "passive"))
      (node (ref "F1") (pin "2") (pinfunction "2_2") (pintype "passive"))
      (node (ref "Q5") (pin "1") (pinfunction "S_1") (pintype "passive"))
      (node (ref "Q5") (pin "2") (pinfunction "S_2") (pintype "passive"))
      (node (ref "Q5") (pin "3") (pinfunction "S_3") (pintype "passive"))
      (node (ref "U6") (pin "2") (pinfunction "SOURCE_2") (pintype "passive"))
      (node (ref "U6") (pin "4") (pinfunction "IN_4") (pintype "passive"))
    )
    (net (code "37") (name "V_Bat_Pro") (class "Default")
      (node (ref "C10") (pin "2") (pinfunction "2_2") (pintype "passive"))
      (node (ref "C11") (pin "2") (pinfunction "2_2") (pintype "passive"))
      (node (ref "C20") (pin "2") (pinfunction "2_2") (pintype "passive"))
      (node (ref "C21") (pin "1") (pinfunction "1_1") (pintype "passive"))
      (node (ref "C23") (pin "1") (pinfunction "1_1") (pintype "passive"))
      (node (ref "C8") (pin "2") (pinfunction "2_2") (pintype "passive"))
      (node (ref "C9") (pin "2") (pinfunction "2_2") (pintype "passive"))
      (node (ref "J10") (pin "1") (pinfunction "P_1") (pintype "passive"))
      (node (ref "J11") (pin "1") (pinfunction "P_1") (pintype "passive"))
      (node (ref "NT2") (pin "1") (pinfunction "1_1") (pintype "passive"))
      (node (ref "NT3") (pin "1") (pinfunction "1_1") (pintype "passive"))
      (node (ref "R16") (pin "2") (pinfunction "2_2") (pintype "passive"))
      (node (ref "RS2") (pin "2") (pinfunction "2_2") (pintype "passive"))
      (node (ref "U3") (pin "10") (pinfunction "VIN_1_10") (pintype "passive"))
      (node (ref "U3") (pin "11") (pinfunction "VIN_2_11") (pintype "passive"))
      (node (ref "U3") (pin "12") (pinfunction "VIN_3_12") (pintype "passive"))
      (node (ref "U4") (pin "10") (pinfunction "VIN_1_10") (pintype "passive"))
      (node (ref "U4") (pin "11") (pinfunction "VIN_2_11") (pintype "passive"))
      (node (ref "U4") (pin "12") (pinfunction "VIN_3_12") (pintype "passive"))
    )
    (net (code "38") (name "unconnected-(J4-PWM-Pad1)") (class "Default")
      (node (ref "J4") (pin "1") (pinfunction "PWM_1") (pintype "passive+no_connect"))
    )
    (net (code "39") (name "unconnected-(J5-PWM-Pad1)") (class "Default")
      (node (ref "J5") (pin "1") (pinfunction "PWM_1") (pintype "passive+no_connect"))
    )
    (net (code "40") (name "unconnected-(J6-PWM-Pad1)") (class "Default")
      (node (ref "J6") (pin "1") (pinfunction "PWM_1") (pintype "passive+no_connect"))
    )
    (net (code "41") (name "unconnected-(J7-PWM-Pad1)") (class "Default")
      (node (ref "J7") (pin "1") (pinfunction "PWM_1") (pintype "passive+no_connect"))
    )
    (net (code "42") (name "unconnected-(J8-PWM-Pad1)") (class "Default")
      (node (ref "J8") (pin "1") (pinfunction "PWM_1") (pintype "passive+no_connect"))
    )
    (net (code "43") (name "unconnected-(J9-PWM-Pad1)") (class "Default")
      (node (ref "J9") (pin "1") (pinfunction "PWM_1") (pintype "passive+no_connect"))
    )
    (net (code "44") (name "unconnected-(U5-ENOUT-Pad11)") (class "Default")
      (node (ref "U5") (pin "11") (pinfunction "ENOUT_11") (pintype "passive+no_connect"))
    )
    (net (code "45") (name "unconnected-(U5-FLT-Pad10)") (class "Default")
      (node (ref "U5") (pin "10") (pinfunction "FLT_10") (pintype "passive+no_connect"))
    )
    (net (code "46") (name "unconnected-(U6-NC-Pad3)") (class "Default")
      (node (ref "U6") (pin "3") (pinfunction "NC_3") (pintype "passive+no_connect"))
    )
    (net (code "47") (name "unconnected-(U6-NC-Pad7)") (class "Default")
      (node (ref "U6") (pin "7") (pinfunction "NC_7") (pintype "passive+no_connect"))
    )
    (net (code "48") (name "unconnected-(U6-SHDN-Pad5)") (class "Default")
      (node (ref "U6") (pin "5") (pinfunction "SHDN_5") (pintype "passive+no_connect"))
    )
  )
)
